# pic32.net
KiCad netlist of a schematic drawn in EAGLE
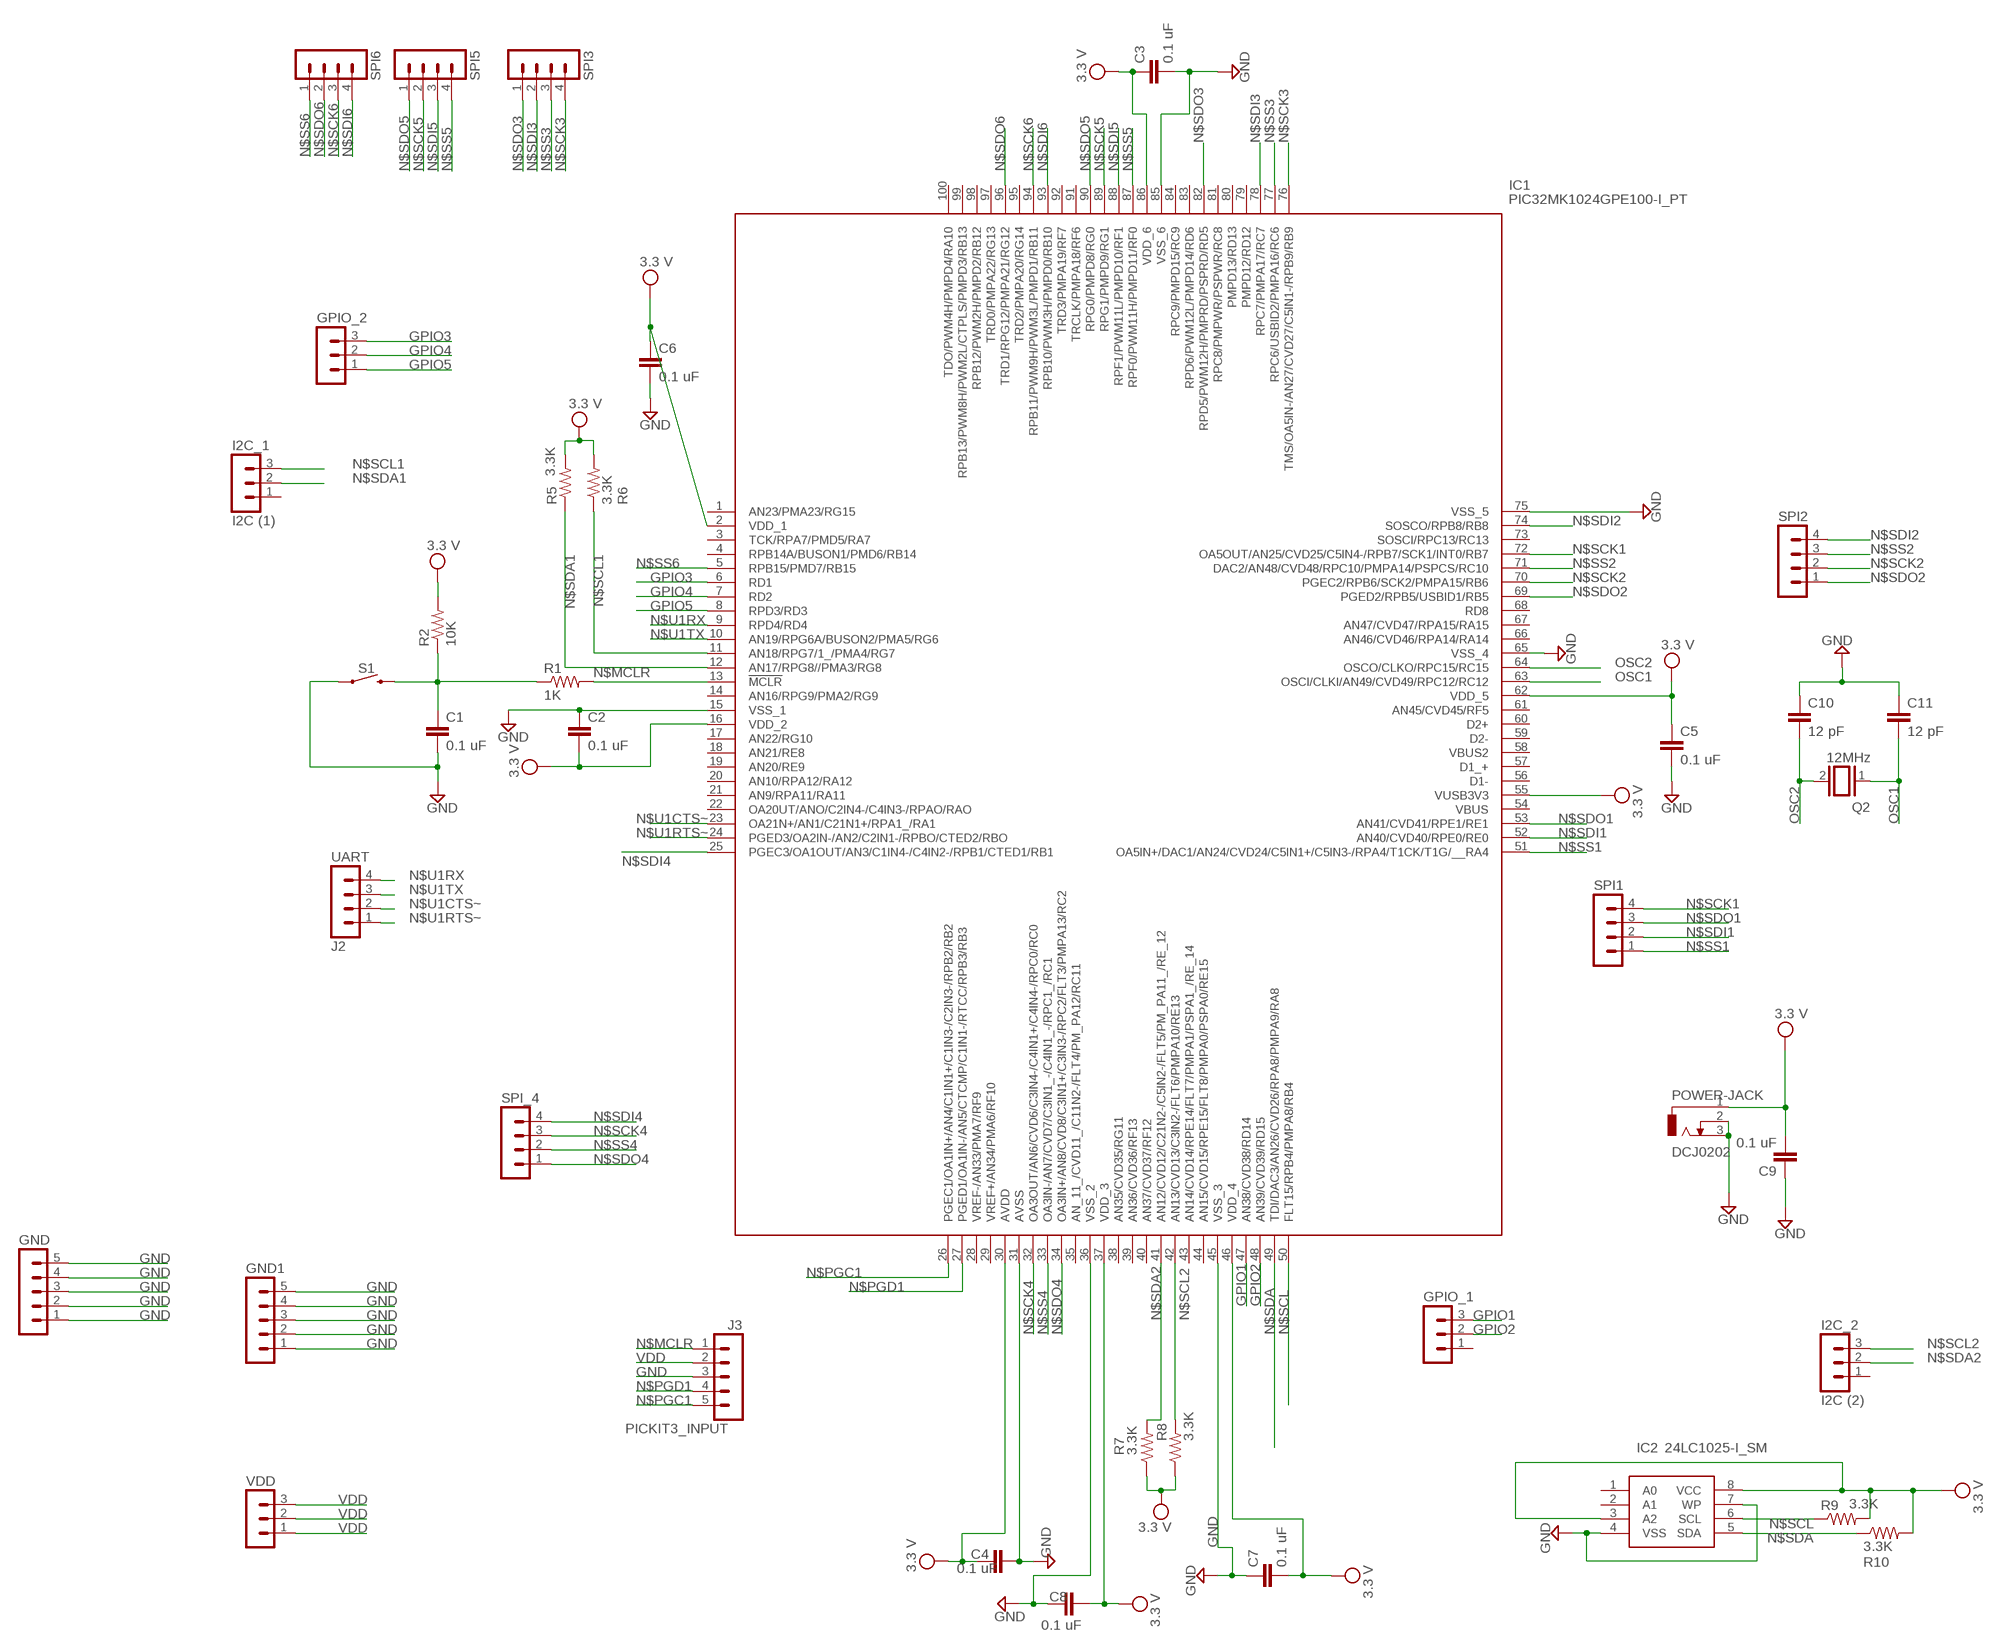
[diagram p0: schematic, sheet 1, part 1 of 2]
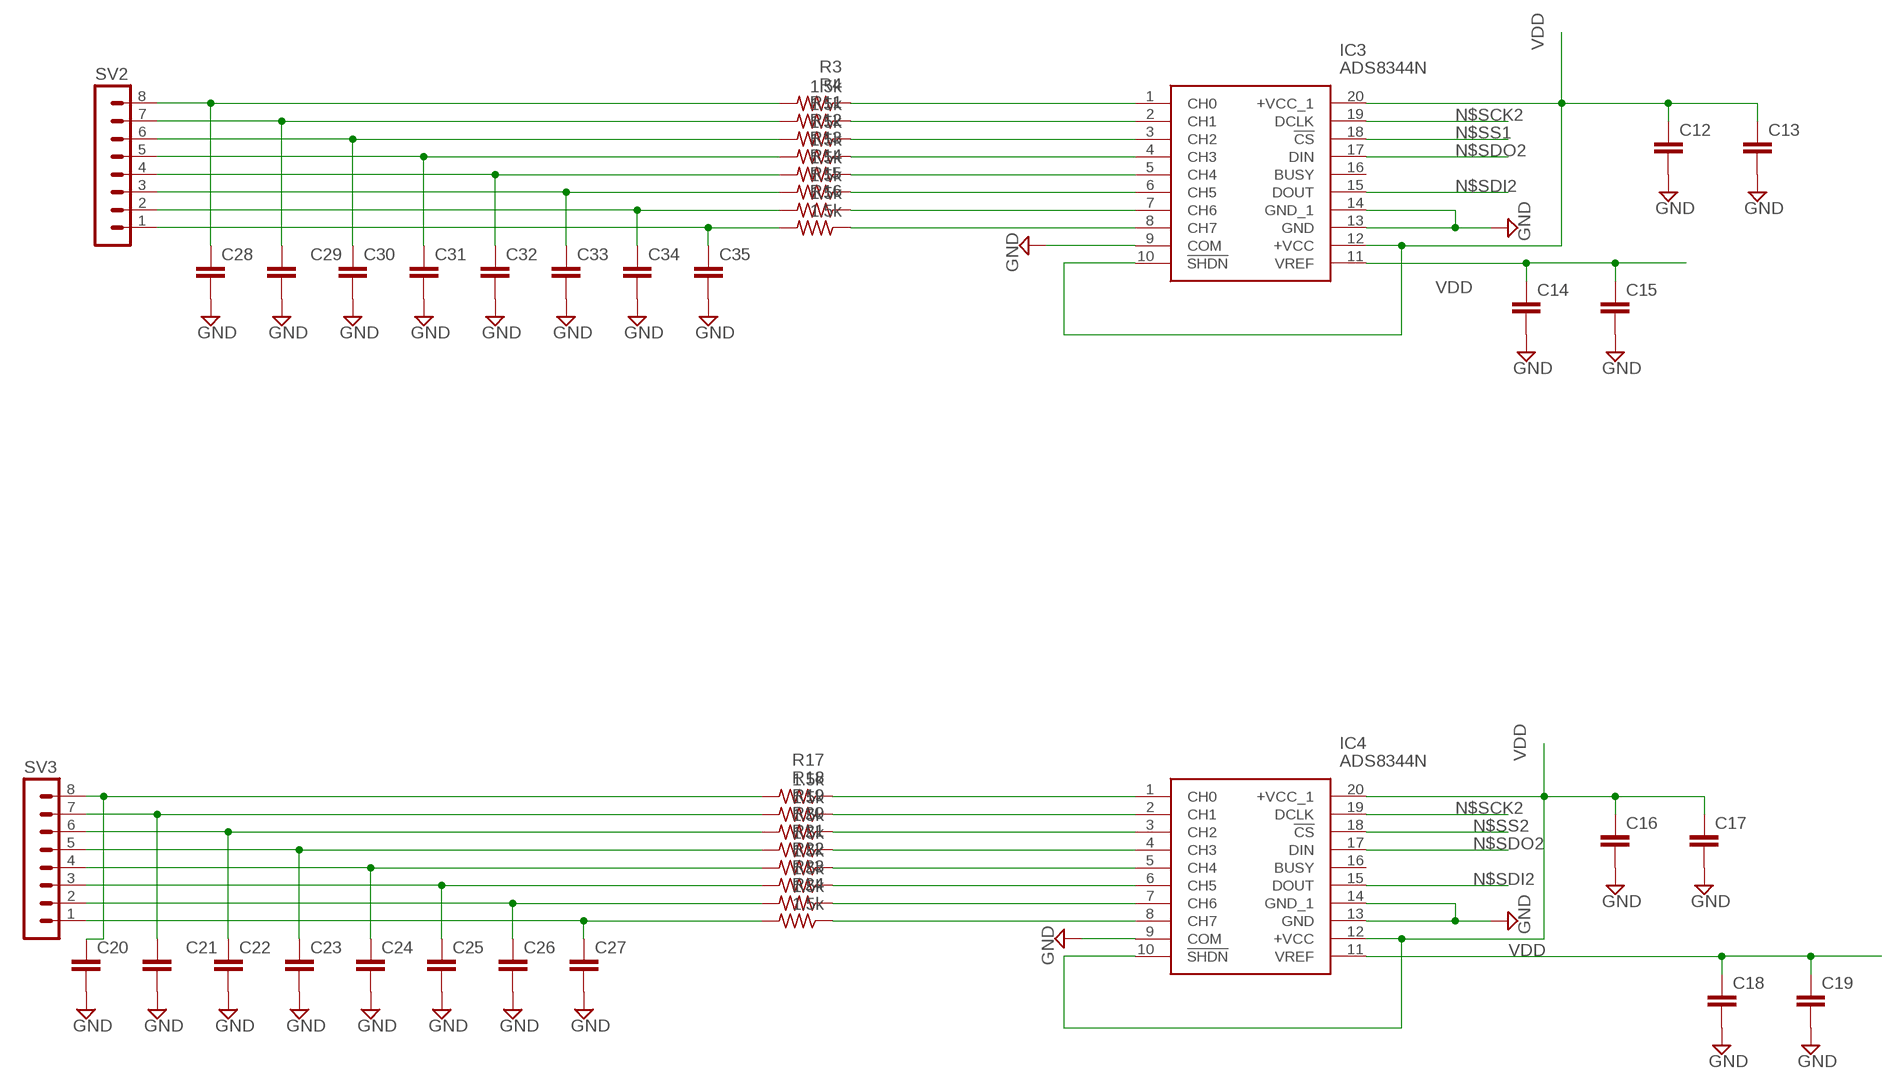
[diagram p1: schematic, sheet 1, part 2 of 2]

(export (version "E")
  (design (tool "Eeschema 10.0.6"))
  (components
    (comp (ref "C1")
      (value "0.1 uF")
      (footprint "eagle-import:C025-025X050")
      (libsource (lib "eagle-import") (part "C-EU025-025X050"))
    )
    (comp (ref "C2")
      (value "0.1 uF")
      (footprint "eagle-import:C025-025X050")
      (libsource (lib "eagle-import") (part "C-EU025-025X050"))
    )
    (comp (ref "C3")
      (value "0.1 uF")
      (footprint "eagle-import:C025-025X050")
      (libsource (lib "eagle-import") (part "C-EU025-025X050"))
    )
    (comp (ref "C4")
      (value "0.1 uF")
      (footprint "eagle-import:C025-025X050")
      (libsource (lib "eagle-import") (part "C-EU025-025X050"))
    )
    (comp (ref "C5")
      (value "0.1 uF")
      (footprint "eagle-import:C025-025X050")
      (libsource (lib "eagle-import") (part "C-EU025-025X050"))
    )
    (comp (ref "C6")
      (value "0.1 uF")
      (footprint "eagle-import:C025-025X050")
      (libsource (lib "eagle-import") (part "C-EU025-025X050"))
    )
    (comp (ref "C7")
      (value "0.1 uF")
      (footprint "eagle-import:C025-025X050")
      (libsource (lib "eagle-import") (part "C-EU025-025X050"))
    )
    (comp (ref "C8")
      (value "0.1 uF")
      (footprint "eagle-import:C025-025X050")
      (libsource (lib "eagle-import") (part "C-EU025-025X050"))
    )
    (comp (ref "C9")
      (value "0.1 uF")
      (footprint "eagle-import:C025-025X050")
      (libsource (lib "eagle-import") (part "C-EU025-025X050"))
    )
    (comp (ref "C10")
      (value "12 pF")
      (footprint "eagle-import:C025-025X050")
      (libsource (lib "eagle-import") (part "C-EU025-025X050"))
    )
    (comp (ref "C11")
      (value "12 pF")
      (footprint "eagle-import:C025-025X050")
      (libsource (lib "eagle-import") (part "C-EU025-025X050"))
    )
    (comp (ref "C12")
      (value "0.1 uF")
      (footprint "eagle-import:C025-025X050")
      (libsource (lib "eagle-import") (part "C-EU025-025X050"))
    )
    (comp (ref "C13")
      (value "0.1 uF")
      (footprint "eagle-import:C025-025X050")
      (libsource (lib "eagle-import") (part "C-EU025-025X050"))
    )
    (comp (ref "C14")
      (value "0.1 uF")
      (footprint "eagle-import:C025-025X050")
      (libsource (lib "eagle-import") (part "C-EU025-025X050"))
    )
    (comp (ref "C15")
      (value "0.1 uF")
      (footprint "eagle-import:C025-025X050")
      (libsource (lib "eagle-import") (part "C-EU025-025X050"))
    )
    (comp (ref "C16")
      (value "0.1 uF")
      (footprint "eagle-import:C025-025X050")
      (libsource (lib "eagle-import") (part "C-EU025-025X050"))
    )
    (comp (ref "C17")
      (value "0.1 uF")
      (footprint "eagle-import:C025-025X050")
      (libsource (lib "eagle-import") (part "C-EU025-025X050"))
    )
    (comp (ref "C18")
      (value "0.1 uF")
      (footprint "eagle-import:C025-025X050")
      (libsource (lib "eagle-import") (part "C-EU025-025X050"))
    )
    (comp (ref "C19")
      (value "0.1 uF")
      (footprint "eagle-import:C025-025X050")
      (libsource (lib "eagle-import") (part "C-EU025-025X050"))
    )
    (comp (ref "C20")
      (value "0.1 uF")
      (footprint "eagle-import:C025-025X050")
      (libsource (lib "eagle-import") (part "C-EU025-025X050"))
    )
    (comp (ref "C21")
      (value "0.1 uF")
      (footprint "eagle-import:C025-025X050")
      (libsource (lib "eagle-import") (part "C-EU025-025X050"))
    )
    (comp (ref "C22")
      (value "0.1 uF")
      (footprint "eagle-import:C025-025X050")
      (libsource (lib "eagle-import") (part "C-EU025-025X050"))
    )
    (comp (ref "C23")
      (value "0.1 uF")
      (footprint "eagle-import:C025-025X050")
      (libsource (lib "eagle-import") (part "C-EU025-025X050"))
    )
    (comp (ref "C24")
      (value "0.1 uF")
      (footprint "eagle-import:C025-025X050")
      (libsource (lib "eagle-import") (part "C-EU025-025X050"))
    )
    (comp (ref "C25")
      (value "0.1 uF")
      (footprint "eagle-import:C025-025X050")
      (libsource (lib "eagle-import") (part "C-EU025-025X050"))
    )
    (comp (ref "C26")
      (value "0.1 uF")
      (footprint "eagle-import:C025-025X050")
      (libsource (lib "eagle-import") (part "C-EU025-025X050"))
    )
    (comp (ref "C27")
      (value "0.1 uF")
      (footprint "eagle-import:C025-025X050")
      (libsource (lib "eagle-import") (part "C-EU025-025X050"))
    )
    (comp (ref "C28")
      (value "0.1 uF")
      (footprint "eagle-import:C025-025X050")
      (libsource (lib "eagle-import") (part "C-EU025-025X050"))
    )
    (comp (ref "C29")
      (value "0.1 uF")
      (footprint "eagle-import:C025-025X050")
      (libsource (lib "eagle-import") (part "C-EU025-025X050"))
    )
    (comp (ref "C30")
      (value "0.1 uF")
      (footprint "eagle-import:C025-025X050")
      (libsource (lib "eagle-import") (part "C-EU025-025X050"))
    )
    (comp (ref "C31")
      (value "0.1 uF")
      (footprint "eagle-import:C025-025X050")
      (libsource (lib "eagle-import") (part "C-EU025-025X050"))
    )
    (comp (ref "C32")
      (value "0.1 uF")
      (footprint "eagle-import:C025-025X050")
      (libsource (lib "eagle-import") (part "C-EU025-025X050"))
    )
    (comp (ref "C33")
      (value "0.1 uF")
      (footprint "eagle-import:C025-025X050")
      (libsource (lib "eagle-import") (part "C-EU025-025X050"))
    )
    (comp (ref "C34")
      (value "0.1 uF")
      (footprint "eagle-import:C025-025X050")
      (libsource (lib "eagle-import") (part "C-EU025-025X050"))
    )
    (comp (ref "C35")
      (value "0.1 uF")
      (footprint "eagle-import:C025-025X050")
      (libsource (lib "eagle-import") (part "C-EU025-025X050"))
    )
    (comp (ref "GND")
      (value "MA05-1")
      (footprint "eagle-import:MA05-1")
      (libsource (lib "eagle-import") (part "MA05-1"))
    )
    (comp (ref "GND1")
      (value "MA05-1")
      (footprint "eagle-import:MA05-1")
      (libsource (lib "eagle-import") (part "MA05-1"))
    )
    (comp (ref "GPIO_1")
      (value "MA03-1")
      (footprint "eagle-import:MA03-1")
      (libsource (lib "eagle-import") (part "MA03-1"))
    )
    (comp (ref "GPIO_2")
      (value "MA03-1")
      (footprint "eagle-import:MA03-1")
      (libsource (lib "eagle-import") (part "MA03-1"))
    )
    (comp (ref "I2C_1")
      (value "I2C (1)")
      (footprint "eagle-import:MA03-1")
      (libsource (lib "eagle-import") (part "MA03-1"))
    )
    (comp (ref "I2C_2")
      (value "I2C (2)")
      (footprint "eagle-import:MA03-1")
      (libsource (lib "eagle-import") (part "MA03-1"))
    )
    (comp (ref "IC1")
      (value "PIC32MK1024GPE100-I_PT")
      (footprint "eagle-import:QFP40P1400X1400X120-100N")
      (fields
        (field (name "MANUFACTURER_PART_NUMBER") "PIC32MK1024GPE100-I/PT")
        (field (name "MOUSER_PART_NUMBER") "579-2MK1024GPE100IPT")
      )
      (libsource (lib "eagle-import") (part "PIC32MK1024GPE100-I_PT"))
    )
    (comp (ref "IC2")
      (value "24LC1025-I_SM")
      (footprint "eagle-import:SOIC127P794X203-8N")
      (fields
        (field (name "MANUFACTURER_PART_NUMBER") "24LC1025-I/SM")
        (field (name "MOUSER_PART_NUMBER") "579-24LC1025-I/SM")
      )
      (libsource (lib "eagle-import") (part "24LC1025-I_SM"))
    )
    (comp (ref "IC3")
      (value "ADS8344N")
      (footprint "eagle-import:SOP65P780X200-20N")
      (fields (field (name "MOUSER_PART_NUMBER") "595-ADS8344N"))
      (libsource (lib "eagle-import") (part "ADS8344N"))
    )
    (comp (ref "IC4")
      (value "ADS8344N")
      (footprint "eagle-import:SOP65P780X200-20N")
      (fields (field (name "MOUSER_PART_NUMBER") "595-ADS8344N"))
      (libsource (lib "eagle-import") (part "ADS8344N"))
    )
    (comp (ref "PICKIT3_INPUT")
      (value "J3")
      (footprint "eagle-import:MA05-1")
      (libsource (lib "eagle-import") (part "MA05-1"))
    )
    (comp (ref "POWER-JACK")
      (value "DCJ0202")
      (footprint "eagle-import:DCJ0202")
      (libsource (lib "eagle-import") (part "DCJ0202"))
    )
    (comp (ref "Q2")
      (value "12MHz")
      (footprint "eagle-import:QS")
      (libsource (lib "eagle-import") (part "XTAL/S"))
    )
    (comp (ref "R1")
      (value "1K")
      (footprint "eagle-import:0207_7")
      (libsource (lib "eagle-import") (part "R-US_0207/7"))
    )
    (comp (ref "R2")
      (value "10K")
      (footprint "eagle-import:0207_7")
      (libsource (lib "eagle-import") (part "R-US_0207/7"))
    )
    (comp (ref "R3")
      (value "1.5k")
      (footprint "eagle-import:0207_7")
      (libsource (lib "eagle-import") (part "R-US_0207/7"))
    )
    (comp (ref "R4")
      (value "1.5k")
      (footprint "eagle-import:0207_7")
      (libsource (lib "eagle-import") (part "R-US_0207/7"))
    )
    (comp (ref "R5")
      (value "3.3K")
      (footprint "eagle-import:0207_7")
      (libsource (lib "eagle-import") (part "R-US_0207/7"))
    )
    (comp (ref "R6")
      (value "3.3K")
      (footprint "eagle-import:0207_7")
      (libsource (lib "eagle-import") (part "R-US_0207/7"))
    )
    (comp (ref "R7")
      (value "3.3K")
      (footprint "eagle-import:0207_7")
      (libsource (lib "eagle-import") (part "R-US_0207/7"))
    )
    (comp (ref "R8")
      (value "3.3K")
      (footprint "eagle-import:0207_7")
      (libsource (lib "eagle-import") (part "R-US_0207/7"))
    )
    (comp (ref "R9")
      (value "3.3K")
      (footprint "eagle-import:0207_7")
      (libsource (lib "eagle-import") (part "R-US_0207/7"))
    )
    (comp (ref "R10")
      (value "3.3K")
      (footprint "eagle-import:0207_7")
      (libsource (lib "eagle-import") (part "R-US_0207/7"))
    )
    (comp (ref "R11")
      (value "1.5k")
      (footprint "eagle-import:0207_7")
      (libsource (lib "eagle-import") (part "R-US_0207/7"))
    )
    (comp (ref "R12")
      (value "1.5k")
      (footprint "eagle-import:0207_7")
      (libsource (lib "eagle-import") (part "R-US_0207/7"))
    )
    (comp (ref "R13")
      (value "1.5k")
      (footprint "eagle-import:0207_7")
      (libsource (lib "eagle-import") (part "R-US_0207/7"))
    )
    (comp (ref "R14")
      (value "1.5k")
      (footprint "eagle-import:0207_7")
      (libsource (lib "eagle-import") (part "R-US_0207/7"))
    )
    (comp (ref "R15")
      (value "1.5k")
      (footprint "eagle-import:0207_7")
      (libsource (lib "eagle-import") (part "R-US_0207/7"))
    )
    (comp (ref "R16")
      (value "1.5k")
      (footprint "eagle-import:0207_7")
      (libsource (lib "eagle-import") (part "R-US_0207/7"))
    )
    (comp (ref "R17")
      (value "1.5k")
      (footprint "eagle-import:0207_7")
      (libsource (lib "eagle-import") (part "R-US_0207/7"))
    )
    (comp (ref "R18")
      (value "1.5k")
      (footprint "eagle-import:0207_7")
      (libsource (lib "eagle-import") (part "R-US_0207/7"))
    )
    (comp (ref "R19")
      (value "1.5k")
      (footprint "eagle-import:0207_7")
      (libsource (lib "eagle-import") (part "R-US_0207/7"))
    )
    (comp (ref "R20")
      (value "1.5k")
      (footprint "eagle-import:0207_7")
      (libsource (lib "eagle-import") (part "R-US_0207/7"))
    )
    (comp (ref "R21")
      (value "1.5k")
      (footprint "eagle-import:0207_7")
      (libsource (lib "eagle-import") (part "R-US_0207/7"))
    )
    (comp (ref "R22")
      (value "1.5k")
      (footprint "eagle-import:0207_7")
      (libsource (lib "eagle-import") (part "R-US_0207/7"))
    )
    (comp (ref "R23")
      (value "1.5k")
      (footprint "eagle-import:0207_7")
      (libsource (lib "eagle-import") (part "R-US_0207/7"))
    )
    (comp (ref "R24")
      (value "1.5k")
      (footprint "eagle-import:0207_7")
      (libsource (lib "eagle-import") (part "R-US_0207/7"))
    )
    (comp (ref "S1")
      (value "MOMENTARY-SWITCH-SPST-SMD-6.2MM-TALL")
      (footprint "eagle-import:TACTILE_SWITCH_SMD_6.2MM_TALL")
      (libsource (lib "eagle-import") (part "MOMENTARY-SWITCH-SPST-SMD-6.2MM-TALL"))
    )
    (comp (ref "SPI1")
      (value "MA04-1")
      (footprint "eagle-import:MA04-1")
      (libsource (lib "eagle-import") (part "MA04-1"))
    )
    (comp (ref "SPI2")
      (value "MA04-1")
      (footprint "eagle-import:MA04-1")
      (libsource (lib "eagle-import") (part "MA04-1"))
    )
    (comp (ref "SPI3")
      (value "MA04-1")
      (footprint "eagle-import:MA04-1")
      (libsource (lib "eagle-import") (part "MA04-1"))
    )
    (comp (ref "SPI5")
      (value "MA04-1")
      (footprint "eagle-import:MA04-1")
      (libsource (lib "eagle-import") (part "MA04-1"))
    )
    (comp (ref "SPI6")
      (value "MA04-1")
      (footprint "eagle-import:MA04-1")
      (libsource (lib "eagle-import") (part "MA04-1"))
    )
    (comp (ref "SPI_4")
      (value "MA04-1")
      (footprint "eagle-import:MA04-1")
      (libsource (lib "eagle-import") (part "MA04-1"))
    )
    (comp (ref "SV2")
      (value "MA08-1")
      (footprint "eagle-import:MA08-1")
      (libsource (lib "eagle-import") (part "MA08-1"))
    )
    (comp (ref "SV3")
      (value "MA08-1")
      (footprint "eagle-import:MA08-1")
      (libsource (lib "eagle-import") (part "MA08-1"))
    )
    (comp (ref "UART")
      (value "J2")
      (footprint "eagle-import:MA04-1")
      (libsource (lib "eagle-import") (part "MA04-1"))
    )
    (comp (ref "VDD")
      (value "MA03-1")
      (footprint "eagle-import:MA03-1")
      (libsource (lib "eagle-import") (part "MA03-1"))
    )
  )
  (nets
    (net (code "1") (name "/GPIO1") (class "Default")
      (node (ref "GPIO_1") (pin "3") (pinfunction "3_3") (pintype "passive"))
      (node (ref "IC1") (pin "47") (pinfunction "AN38/CVD38/RD14_47") (pintype "bidirectional"))
    )
    (net (code "2") (name "/GPIO2") (class "Default")
      (node (ref "GPIO_1") (pin "2") (pinfunction "2_2") (pintype "passive"))
      (node (ref "IC1") (pin "48") (pinfunction "AN39/CVD39/RD15_48") (pintype "bidirectional"))
    )
    (net (code "3") (name "/GPIO3") (class "Default")
      (node (ref "GPIO_2") (pin "3") (pinfunction "3_3") (pintype "passive"))
      (node (ref "IC1") (pin "6") (pinfunction "RD1_6") (pintype "bidirectional"))
    )
    (net (code "4") (name "/GPIO4") (class "Default")
      (node (ref "GPIO_2") (pin "2") (pinfunction "2_2") (pintype "passive"))
      (node (ref "IC1") (pin "7") (pinfunction "RD2_7") (pintype "bidirectional"))
    )
    (net (code "5") (name "/GPIO5") (class "Default")
      (node (ref "GPIO_2") (pin "1") (pinfunction "1_1") (pintype "passive"))
      (node (ref "IC1") (pin "8") (pinfunction "RPD3/RD3_8") (pintype "bidirectional"))
    )
    (net (code "6") (name "/N$MCLR") (class "Default")
      (node (ref "IC1") (pin "13") (pinfunction "~{MCLR}_13") (pintype "bidirectional"))
      (node (ref "PICKIT3_INPUT") (pin "1") (pinfunction "1_1") (pintype "passive"))
      (node (ref "R1") (pin "2") (pinfunction "2_2") (pintype "passive"))
    )
    (net (code "7") (name "/N$PGC1") (class "Default")
      (node (ref "IC1") (pin "26") (pinfunction "PGEC1/OA1IN+/AN4/C1IN1+/C1IN3-/C2IN3-/RPB2/RB2_26") (pintype "bidirectional"))
      (node (ref "PICKIT3_INPUT") (pin "5") (pinfunction "5_5") (pintype "passive"))
    )
    (net (code "8") (name "/N$PGD1") (class "Default")
      (node (ref "IC1") (pin "27") (pinfunction "PGED1/OA1IN-/AN5/CTCMP/C1IN1-/RTCC/RPB3/RB3_27") (pintype "bidirectional"))
      (node (ref "PICKIT3_INPUT") (pin "4") (pinfunction "4_4") (pintype "passive"))
    )
    (net (code "9") (name "/N$SCK1") (class "Default")
      (node (ref "IC1") (pin "72") (pinfunction "OA5OUT/AN25/CVD25/C5IN4-/RPB7/SCK1/INT0/RB7_72") (pintype "bidirectional"))
      (node (ref "SPI1") (pin "4") (pinfunction "4_4") (pintype "passive"))
    )
    (net (code "10") (name "/N$SCK2") (class "Default")
      (node (ref "IC1") (pin "70") (pinfunction "PGEC2/RPB6/SCK2/PMPA15/RB6_70") (pintype "bidirectional"))
      (node (ref "IC3") (pin "19") (pinfunction "DCLK_19") (pintype "input"))
      (node (ref "IC4") (pin "19") (pinfunction "DCLK_19") (pintype "input"))
      (node (ref "SPI2") (pin "2") (pinfunction "2_2") (pintype "passive"))
    )
    (net (code "11") (name "/N$SCK3") (class "Default")
      (node (ref "IC1") (pin "76") (pinfunction "TMS/OA5IN-/AN27/CVD27/C5IN1-/RPB9/RB9_76") (pintype "bidirectional"))
      (node (ref "SPI3") (pin "4") (pinfunction "4_4") (pintype "passive"))
    )
    (net (code "12") (name "/N$SCK4") (class "Default")
      (node (ref "IC1") (pin "32") (pinfunction "OA3OUT/AN6/CVD6/C3IN4-/C4IN1+/C4IN4-/RPC0/RC0_32") (pintype "bidirectional"))
      (node (ref "SPI_4") (pin "3") (pinfunction "3_3") (pintype "passive"))
    )
    (net (code "13") (name "/N$SCK5") (class "Default")
      (node (ref "IC1") (pin "89") (pinfunction "RPG1/PMPD9/RG1_89") (pintype "bidirectional"))
      (node (ref "SPI5") (pin "2") (pinfunction "2_2") (pintype "passive"))
    )
    (net (code "14") (name "/N$SCK6") (class "Default")
      (node (ref "IC1") (pin "94") (pinfunction "RPB11/PWM9H/PWM3L/PMPD1/RB11_94") (pintype "bidirectional"))
      (node (ref "SPI6") (pin "3") (pinfunction "3_3") (pintype "passive"))
    )
    (net (code "15") (name "/N$SCL") (class "Default")
      (node (ref "IC1") (pin "50") (pinfunction "FLT15/RPB4/PMPA8/RB4_50") (pintype "bidirectional"))
      (node (ref "IC2") (pin "6") (pinfunction "SCL_6") (pintype "bidirectional"))
      (node (ref "R9") (pin "1") (pinfunction "1_1") (pintype "passive"))
    )
    (net (code "16") (name "/N$SCL1") (class "Default")
      (node (ref "I2C_1") (pin "3") (pinfunction "3_3") (pintype "passive"))
      (node (ref "IC1") (pin "11") (pinfunction "AN18/RPG7/1_/PMA4/RG7_11") (pintype "bidirectional"))
      (node (ref "R6") (pin "1") (pinfunction "1_1") (pintype "passive"))
    )
    (net (code "17") (name "/N$SCL2") (class "Default")
      (node (ref "I2C_2") (pin "3") (pinfunction "3_3") (pintype "passive"))
      (node (ref "IC1") (pin "42") (pinfunction "AN13/CVD13/C3IN2-/FLT6/PMPA10/RE13_42") (pintype "bidirectional"))
      (node (ref "R8") (pin "2") (pinfunction "2_2") (pintype "passive"))
    )
    (net (code "18") (name "/N$SDA") (class "Default")
      (node (ref "IC1") (pin "49") (pinfunction "TDI/DAC3/AN26/CVD26/RPA8/PMPA9/RA8_49") (pintype "bidirectional"))
      (node (ref "IC2") (pin "5") (pinfunction "SDA_5") (pintype "bidirectional"))
      (node (ref "R10") (pin "1") (pinfunction "1_1") (pintype "passive"))
    )
    (net (code "19") (name "/N$SDA1") (class "Default")
      (node (ref "I2C_1") (pin "2") (pinfunction "2_2") (pintype "passive"))
      (node (ref "IC1") (pin "12") (pinfunction "AN17/RPG8//PMA3/RG8_12") (pintype "bidirectional"))
      (node (ref "R5") (pin "1") (pinfunction "1_1") (pintype "passive"))
    )
    (net (code "20") (name "/N$SDA2") (class "Default")
      (node (ref "I2C_2") (pin "2") (pinfunction "2_2") (pintype "passive"))
      (node (ref "IC1") (pin "41") (pinfunction "AN12/CVD12/C21N2-/C5IN2-/FLT5/PM_PA11_/RE_12_41") (pintype "bidirectional"))
      (node (ref "R7") (pin "2") (pinfunction "2_2") (pintype "passive"))
    )
    (net (code "21") (name "/N$SDI1") (class "Default")
      (node (ref "IC1") (pin "52") (pinfunction "AN40/CVD40/RPE0/RE0_52") (pintype "bidirectional"))
      (node (ref "SPI1") (pin "2") (pinfunction "2_2") (pintype "passive"))
    )
    (net (code "22") (name "/N$SDI2") (class "Default")
      (node (ref "IC1") (pin "74") (pinfunction "SOSCO/RPB8/RB8_74") (pintype "bidirectional"))
      (node (ref "IC3") (pin "15") (pinfunction "DOUT_15") (pintype "output"))
      (node (ref "IC4") (pin "15") (pinfunction "DOUT_15") (pintype "output"))
      (node (ref "SPI2") (pin "4") (pinfunction "4_4") (pintype "passive"))
    )
    (net (code "23") (name "/N$SDI3") (class "Default")
      (node (ref "IC1") (pin "78") (pinfunction "RPC7/PMPA17/RC7_78") (pintype "bidirectional"))
      (node (ref "SPI3") (pin "2") (pinfunction "2_2") (pintype "passive"))
    )
    (net (code "24") (name "/N$SDI4") (class "Default")
      (node (ref "IC1") (pin "25") (pinfunction "PGEC3/OA1OUT/AN3/C1IN4-/C4IN2-/RPB1/CTED1/RB1_25") (pintype "bidirectional"))
      (node (ref "SPI_4") (pin "4") (pinfunction "4_4") (pintype "passive"))
    )
    (net (code "25") (name "/N$SDI5") (class "Default")
      (node (ref "IC1") (pin "88") (pinfunction "RPF1/PWM11L/PMPD10/RF1_88") (pintype "bidirectional"))
      (node (ref "SPI5") (pin "3") (pinfunction "3_3") (pintype "passive"))
    )
    (net (code "26") (name "/N$SDI6") (class "Default")
      (node (ref "IC1") (pin "93") (pinfunction "RPB10/PWM3H/PMPD0/RB10_93") (pintype "bidirectional"))
      (node (ref "SPI6") (pin "4") (pinfunction "4_4") (pintype "passive"))
    )
    (net (code "27") (name "/N$SDO1") (class "Default")
      (node (ref "IC1") (pin "53") (pinfunction "AN41/CVD41/RPE1/RE1_53") (pintype "bidirectional"))
      (node (ref "SPI1") (pin "3") (pinfunction "3_3") (pintype "passive"))
    )
    (net (code "28") (name "/N$SDO2") (class "Default")
      (node (ref "IC1") (pin "69") (pinfunction "PGED2/RPB5/USBID1/RB5_69") (pintype "bidirectional"))
      (node (ref "IC3") (pin "17") (pinfunction "DIN_17") (pintype "input"))
      (node (ref "IC4") (pin "17") (pinfunction "DIN_17") (pintype "input"))
      (node (ref "SPI2") (pin "1") (pinfunction "1_1") (pintype "passive"))
    )
    (net (code "29") (name "/N$SDO3") (class "Default")
      (node (ref "IC1") (pin "82") (pinfunction "RPD5/PWM12H/PMPRD/PSPRD/RD5_82") (pintype "bidirectional"))
      (node (ref "SPI3") (pin "1") (pinfunction "1_1") (pintype "passive"))
    )
    (net (code "30") (name "/N$SDO4") (class "Default")
      (node (ref "IC1") (pin "34") (pinfunction "OA3IN+/AN8/CVD8/C3IN1+/C3IN3-/RPC2/FLT3/PMPA13/RC2_34") (pintype "bidirectional"))
      (node (ref "SPI_4") (pin "1") (pinfunction "1_1") (pintype "passive"))
    )
    (net (code "31") (name "/N$SDO5") (class "Default")
      (node (ref "IC1") (pin "90") (pinfunction "RPG0/PMPD8/RG0_90") (pintype "bidirectional"))
      (node (ref "SPI5") (pin "1") (pinfunction "1_1") (pintype "passive"))
    )
    (net (code "32") (name "/N$SDO6") (class "Default")
      (node (ref "IC1") (pin "96") (pinfunction "TRD1/RPG12/PMPA21/RG12_96") (pintype "bidirectional"))
      (node (ref "SPI6") (pin "2") (pinfunction "2_2") (pintype "passive"))
    )
    (net (code "33") (name "/N$SS1") (class "Default")
      (node (ref "IC1") (pin "51") (pinfunction "OA5IN+/DAC1/AN24/CVD24/C5IN1+/C5IN3-/RPA4/T1CK/T1G/__RA4_51") (pintype "bidirectional"))
      (node (ref "IC3") (pin "18") (pinfunction "~{CS}_18") (pintype "input"))
      (node (ref "SPI1") (pin "1") (pinfunction "1_1") (pintype "passive"))
    )
    (net (code "34") (name "/N$SS2") (class "Default")
      (node (ref "IC1") (pin "71") (pinfunction "DAC2/AN48/CVD48/RPC10/PMPA14/PSPCS/RC10_71") (pintype "bidirectional"))
      (node (ref "IC4") (pin "18") (pinfunction "~{CS}_18") (pintype "input"))
      (node (ref "SPI2") (pin "3") (pinfunction "3_3") (pintype "passive"))
    )
    (net (code "35") (name "/N$SS3") (class "Default")
      (node (ref "IC1") (pin "77") (pinfunction "RPC6/USBID2/PMPA16/RC6_77") (pintype "bidirectional"))
      (node (ref "SPI3") (pin "3") (pinfunction "3_3") (pintype "passive"))
    )
    (net (code "36") (name "/N$SS4") (class "Default")
      (node (ref "IC1") (pin "33") (pinfunction "OA3IN-/AN7/CVD7/C3IN1_-/C4IN1_-/RPC1_/RC1_33") (pintype "bidirectional"))
      (node (ref "SPI_4") (pin "2") (pinfunction "2_2") (pintype "passive"))
    )
    (net (code "37") (name "/N$SS5") (class "Default")
      (node (ref "IC1") (pin "87") (pinfunction "RPF0/PWM11H/PMPD11/RF0_87") (pintype "bidirectional"))
      (node (ref "SPI5") (pin "4") (pinfunction "4_4") (pintype "passive"))
    )
    (net (code "38") (name "/N$SS6") (class "Default")
      (node (ref "IC1") (pin "5") (pinfunction "RPB15/PMD7/RB15_5") (pintype "bidirectional"))
      (node (ref "SPI6") (pin "1") (pinfunction "1_1") (pintype "passive"))
    )
    (net (code "39") (name "/N$U1CTS~{}") (class "Default")
      (node (ref "IC1") (pin "23") (pinfunction "OA21N+/AN1/C21N1+/RPA1_/RA1_23") (pintype "bidirectional"))
      (node (ref "UART") (pin "2") (pinfunction "2_2") (pintype "passive"))
    )
    (net (code "40") (name "/N$U1RTS~{}") (class "Default")
      (node (ref "IC1") (pin "24") (pinfunction "PGED3/OA2IN-/AN2/C2IN1-/RPBO/CTED2/RBO_24") (pintype "bidirectional"))
      (node (ref "UART") (pin "1") (pinfunction "1_1") (pintype "passive"))
    )
    (net (code "41") (name "/N$U1RX") (class "Default")
      (node (ref "IC1") (pin "9") (pinfunction "RPD4/RD4_9") (pintype "bidirectional"))
      (node (ref "UART") (pin "4") (pinfunction "4_4") (pintype "passive"))
    )
    (net (code "42") (name "/N$U1TX") (class "Default")
      (node (ref "IC1") (pin "10") (pinfunction "AN19/RPG6A/BUSON2/PMA5/RG6_10") (pintype "bidirectional"))
      (node (ref "UART") (pin "3") (pinfunction "3_3") (pintype "passive"))
    )
    (net (code "43") (name "/OSC1") (class "Default")
      (node (ref "C11") (pin "2") (pinfunction "2_2") (pintype "passive"))
      (node (ref "IC1") (pin "63") (pinfunction "OSCI/CLKI/AN49/CVD49/RPC12/RC12_63") (pintype "bidirectional"))
      (node (ref "Q2") (pin "1") (pinfunction "1_1") (pintype "passive"))
    )
    (net (code "44") (name "/OSC2") (class "Default")
      (node (ref "C10") (pin "2") (pinfunction "2_2") (pintype "passive"))
      (node (ref "IC1") (pin "64") (pinfunction "OSCO/CLKO/RPC15/RC15_64") (pintype "bidirectional"))
      (node (ref "Q2") (pin "2") (pinfunction "2_2") (pintype "passive"))
    )
    (net (code "45") (name "3.3 V") (class "Default")
      (node (ref "C12") (pin "1") (pinfunction "1_1") (pintype "passive"))
      (node (ref "C13") (pin "1") (pinfunction "1_1") (pintype "passive"))
      (node (ref "C14") (pin "1") (pinfunction "1_1") (pintype "passive"))
      (node (ref "C15") (pin "1") (pinfunction "1_1") (pintype "passive"))
      (node (ref "C16") (pin "1") (pinfunction "1_1") (pintype "passive"))
      (node (ref "C17") (pin "1") (pinfunction "1_1") (pintype "passive"))
      (node (ref "C18") (pin "1") (pinfunction "1_1") (pintype "passive"))
      (node (ref "C19") (pin "1") (pinfunction "1_1") (pintype "passive"))
      (node (ref "C2") (pin "2") (pinfunction "2_2") (pintype "passive"))
      (node (ref "C3") (pin "1") (pinfunction "1_1") (pintype "passive"))
      (node (ref "C4") (pin "2") (pinfunction "2_2") (pintype "passive"))
      (node (ref "C5") (pin "1") (pinfunction "1_1") (pintype "passive"))
      (node (ref "C6") (pin "1") (pinfunction "1_1") (pintype "passive"))
      (node (ref "C7") (pin "2") (pinfunction "2_2") (pintype "passive"))
      (node (ref "C8") (pin "2") (pinfunction "2_2") (pintype "passive"))
      (node (ref "C9") (pin "2") (pinfunction "2_2") (pintype "passive"))
      (node (ref "IC1") (pin "16") (pinfunction "VDD_2_16") (pintype "bidirectional"))
      (node (ref "IC1") (pin "2") (pinfunction "VDD_1_2") (pintype "bidirectional"))
      (node (ref "IC1") (pin "30") (pinfunction "AVDD_30") (pintype "bidirectional"))
      (node (ref "IC1") (pin "37") (pinfunction "VDD_3_37") (pintype "bidirectional"))
      (node (ref "IC1") (pin "46") (pinfunction "VDD_4_46") (pintype "bidirectional"))
      (node (ref "IC1") (pin "55") (pinfunction "VUSB3V3_55") (pintype "bidirectional"))
      (node (ref "IC1") (pin "62") (pinfunction "VDD_5_62") (pintype "bidirectional"))
      (node (ref "IC1") (pin "86") (pinfunction "VDD_6_86") (pintype "bidirectional"))
      (node (ref "IC2") (pin "3") (pinfunction "A2_3") (pintype "bidirectional"))
      (node (ref "IC2") (pin "8") (pinfunction "VCC_8") (pintype "power_in"))
      (node (ref "IC3") (pin "10") (pinfunction "~{SHDN}_10") (pintype "bidirectional"))
      (node (ref "IC3") (pin "11") (pinfunction "VREF_11") (pintype "input"))
      (node (ref "IC3") (pin "12") (pinfunction "+VCC_12") (pintype "power_in"))
      (node (ref "IC3") (pin "20") (pinfunction "+VCC_1_20") (pintype "power_in"))
      (node (ref "IC4") (pin "10") (pinfunction "~{SHDN}_10") (pintype "bidirectional"))
      (node (ref "IC4") (pin "11") (pinfunction "VREF_11") (pintype "input"))
      (node (ref "IC4") (pin "12") (pinfunction "+VCC_12") (pintype "power_in"))
      (node (ref "IC4") (pin "20") (pinfunction "+VCC_1_20") (pintype "power_in"))
      (node (ref "PICKIT3_INPUT") (pin "2") (pinfunction "2_2") (pintype "passive"))
      (node (ref "POWER-JACK") (pin "1") (pinfunction "1_1") (pintype "passive"))
      (node (ref "R10") (pin "2") (pinfunction "2_2") (pintype "passive"))
      (node (ref "R2") (pin "2") (pinfunction "2_2") (pintype "passive"))
      (node (ref "R5") (pin "2") (pinfunction "2_2") (pintype "passive"))
      (node (ref "R6") (pin "2") (pinfunction "2_2") (pintype "passive"))
      (node (ref "R7") (pin "1") (pinfunction "1_1") (pintype "passive"))
      (node (ref "R8") (pin "1") (pinfunction "1_1") (pintype "passive"))
      (node (ref "R9") (pin "2") (pinfunction "2_2") (pintype "passive"))
      (node (ref "VDD") (pin "1") (pinfunction "1_1") (pintype "passive"))
      (node (ref "VDD") (pin "2") (pinfunction "2_2") (pintype "passive"))
      (node (ref "VDD") (pin "3") (pinfunction "3_3") (pintype "passive"))
    )
    (net (code "46") (name "GND") (class "Default")
      (node (ref "C1") (pin "2") (pinfunction "2_2") (pintype "passive"))
      (node (ref "C10") (pin "1") (pinfunction "1_1") (pintype "passive"))
      (node (ref "C11") (pin "1") (pinfunction "1_1") (pintype "passive"))
      (node (ref "C12") (pin "2") (pinfunction "2_2") (pintype "passive"))
      (node (ref "C13") (pin "2") (pinfunction "2_2") (pintype "passive"))
      (node (ref "C14") (pin "2") (pinfunction "2_2") (pintype "passive"))
      (node (ref "C15") (pin "2") (pinfunction "2_2") (pintype "passive"))
      (node (ref "C16") (pin "2") (pinfunction "2_2") (pintype "passive"))
      (node (ref "C17") (pin "2") (pinfunction "2_2") (pintype "passive"))
      (node (ref "C18") (pin "2") (pinfunction "2_2") (pintype "passive"))
      (node (ref "C19") (pin "2") (pinfunction "2_2") (pintype "passive"))
      (node (ref "C2") (pin "1") (pinfunction "1_1") (pintype "passive"))
      (node (ref "C20") (pin "2") (pinfunction "2_2") (pintype "passive"))
      (node (ref "C21") (pin "2") (pinfunction "2_2") (pintype "passive"))
      (node (ref "C22") (pin "2") (pinfunction "2_2") (pintype "passive"))
      (node (ref "C23") (pin "2") (pinfunction "2_2") (pintype "passive"))
      (node (ref "C24") (pin "2") (pinfunction "2_2") (pintype "passive"))
      (node (ref "C25") (pin "2") (pinfunction "2_2") (pintype "passive"))
      (node (ref "C26") (pin "2") (pinfunction "2_2") (pintype "passive"))
      (node (ref "C27") (pin "2") (pinfunction "2_2") (pintype "passive"))
      (node (ref "C28") (pin "2") (pinfunction "2_2") (pintype "passive"))
      (node (ref "C29") (pin "2") (pinfunction "2_2") (pintype "passive"))
      (node (ref "C3") (pin "2") (pinfunction "2_2") (pintype "passive"))
      (node (ref "C30") (pin "2") (pinfunction "2_2") (pintype "passive"))
      (node (ref "C31") (pin "2") (pinfunction "2_2") (pintype "passive"))
      (node (ref "C32") (pin "2") (pinfunction "2_2") (pintype "passive"))
      (node (ref "C33") (pin "2") (pinfunction "2_2") (pintype "passive"))
      (node (ref "C34") (pin "2") (pinfunction "2_2") (pintype "passive"))
      (node (ref "C35") (pin "2") (pinfunction "2_2") (pintype "passive"))
      (node (ref "C4") (pin "1") (pinfunction "1_1") (pintype "passive"))
      (node (ref "C5") (pin "2") (pinfunction "2_2") (pintype "passive"))
      (node (ref "C6") (pin "2") (pinfunction "2_2") (pintype "passive"))
      (node (ref "C7") (pin "1") (pinfunction "1_1") (pintype "passive"))
      (node (ref "C8") (pin "1") (pinfunction "1_1") (pintype "passive"))
      (node (ref "C9") (pin "1") (pinfunction "1_1") (pintype "passive"))
      (node (ref "GND") (pin "1") (pinfunction "1_1") (pintype "passive"))
      (node (ref "GND") (pin "2") (pinfunction "2_2") (pintype "passive"))
      (node (ref "GND") (pin "3") (pinfunction "3_3") (pintype "passive"))
      (node (ref "GND") (pin "4") (pinfunction "4_4") (pintype "passive"))
      (node (ref "GND") (pin "5") (pinfunction "5_5") (pintype "passive"))
      (node (ref "GND1") (pin "1") (pinfunction "1_1") (pintype "passive"))
      (node (ref "GND1") (pin "2") (pinfunction "2_2") (pintype "passive"))
      (node (ref "GND1") (pin "3") (pinfunction "3_3") (pintype "passive"))
      (node (ref "GND1") (pin "4") (pinfunction "4_4") (pintype "passive"))
      (node (ref "GND1") (pin "5") (pinfunction "5_5") (pintype "passive"))
      (node (ref "IC1") (pin "15") (pinfunction "VSS_1_15") (pintype "bidirectional"))
      (node (ref "IC1") (pin "31") (pinfunction "AVSS_31") (pintype "bidirectional"))
      (node (ref "IC1") (pin "36") (pinfunction "VSS_2_36") (pintype "bidirectional"))
      (node (ref "IC1") (pin "45") (pinfunction "VSS_3_45") (pintype "bidirectional"))
      (node (ref "IC1") (pin "65") (pinfunction "VSS_4_65") (pintype "bidirectional"))
      (node (ref "IC1") (pin "75") (pinfunction "VSS_5_75") (pintype "bidirectional"))
      (node (ref "IC1") (pin "85") (pinfunction "VSS_6_85") (pintype "bidirectional"))
      (node (ref "IC2") (pin "4") (pinfunction "VSS_4") (pintype "power_in"))
      (node (ref "IC2") (pin "7") (pinfunction "WP_7") (pintype "bidirectional"))
      (node (ref "IC3") (pin "13") (pinfunction "GND_13") (pintype "power_in"))
      (node (ref "IC3") (pin "14") (pinfunction "GND_1_14") (pintype "power_in"))
      (node (ref "IC3") (pin "9") (pinfunction "COM_9") (pintype "bidirectional"))
      (node (ref "IC4") (pin "13") (pinfunction "GND_13") (pintype "power_in"))
      (node (ref "IC4") (pin "14") (pinfunction "GND_1_14") (pintype "power_in"))
      (node (ref "IC4") (pin "9") (pinfunction "COM_9") (pintype "bidirectional"))
      (node (ref "PICKIT3_INPUT") (pin "3") (pinfunction "3_3") (pintype "passive"))
      (node (ref "POWER-JACK") (pin "2") (pinfunction "2_2") (pintype "passive"))
      (node (ref "POWER-JACK") (pin "3") (pinfunction "3_3") (pintype "passive"))
      (node (ref "S1") (pin "A2") (pinfunction "1_A2") (pintype "passive"))
    )
    (net (code "47") (name "Net-(C20-Pad1)") (class "Default")
      (node (ref "C20") (pin "1") (pinfunction "1_1") (pintype "passive"))
      (node (ref "R17") (pin "2") (pinfunction "2_2") (pintype "passive"))
      (node (ref "SV3") (pin "8") (pinfunction "8_8") (pintype "passive"))
    )
    (net (code "48") (name "Net-(C21-Pad1)") (class "Default")
      (node (ref "C21") (pin "1") (pinfunction "1_1") (pintype "passive"))
      (node (ref "R18") (pin "2") (pinfunction "2_2") (pintype "passive"))
      (node (ref "SV3") (pin "7") (pinfunction "7_7") (pintype "passive"))
    )
    (net (code "49") (name "Net-(C22-Pad1)") (class "Default")
      (node (ref "C22") (pin "1") (pinfunction "1_1") (pintype "passive"))
      (node (ref "R19") (pin "2") (pinfunction "2_2") (pintype "passive"))
      (node (ref "SV3") (pin "6") (pinfunction "6_6") (pintype "passive"))
    )
    (net (code "50") (name "Net-(C23-Pad1)") (class "Default")
      (node (ref "C23") (pin "1") (pinfunction "1_1") (pintype "passive"))
      (node (ref "R20") (pin "2") (pinfunction "2_2") (pintype "passive"))
      (node (ref "SV3") (pin "5") (pinfunction "5_5") (pintype "passive"))
    )
    (net (code "51") (name "Net-(C24-Pad1)") (class "Default")
      (node (ref "C24") (pin "1") (pinfunction "1_1") (pintype "passive"))
      (node (ref "R21") (pin "2") (pinfunction "2_2") (pintype "passive"))
      (node (ref "SV3") (pin "4") (pinfunction "4_4") (pintype "passive"))
    )
    (net (code "52") (name "Net-(C25-Pad1)") (class "Default")
      (node (ref "C25") (pin "1") (pinfunction "1_1") (pintype "passive"))
      (node (ref "R22") (pin "2") (pinfunction "2_2") (pintype "passive"))
      (node (ref "SV3") (pin "3") (pinfunction "3_3") (pintype "passive"))
    )
    (net (code "53") (name "Net-(C26-Pad1)") (class "Default")
      (node (ref "C26") (pin "1") (pinfunction "1_1") (pintype "passive"))
      (node (ref "R23") (pin "2") (pinfunction "2_2") (pintype "passive"))
      (node (ref "SV3") (pin "2") (pinfunction "2_2") (pintype "passive"))
    )
    (net (code "54") (name "Net-(C27-Pad1)") (class "Default")
      (node (ref "C27") (pin "1") (pinfunction "1_1") (pintype "passive"))
      (node (ref "R24") (pin "2") (pinfunction "2_2") (pintype "passive"))
      (node (ref "SV3") (pin "1") (pinfunction "1_1") (pintype "passive"))
    )
    (net (code "55") (name "Net-(C28-Pad1)") (class "Default")
      (node (ref "C28") (pin "1") (pinfunction "1_1") (pintype "passive"))
      (node (ref "R3") (pin "2") (pinfunction "2_2") (pintype "passive"))
      (node (ref "SV2") (pin "8") (pinfunction "8_8") (pintype "passive"))
    )
    (net (code "56") (name "Net-(C29-Pad1)") (class "Default")
      (node (ref "C29") (pin "1") (pinfunction "1_1") (pintype "passive"))
      (node (ref "R4") (pin "2") (pinfunction "2_2") (pintype "passive"))
      (node (ref "SV2") (pin "7") (pinfunction "7_7") (pintype "passive"))
    )
    (net (code "57") (name "Net-(C30-Pad1)") (class "Default")
      (node (ref "C30") (pin "1") (pinfunction "1_1") (pintype "passive"))
      (node (ref "R11") (pin "2") (pinfunction "2_2") (pintype "passive"))
      (node (ref "SV2") (pin "6") (pinfunction "6_6") (pintype "passive"))
    )
    (net (code "58") (name "Net-(C31-Pad1)") (class "Default")
      (node (ref "C31") (pin "1") (pinfunction "1_1") (pintype "passive"))
      (node (ref "R12") (pin "2") (pinfunction "2_2") (pintype "passive"))
      (node (ref "SV2") (pin "5") (pinfunction "5_5") (pintype "passive"))
    )
    (net (code "59") (name "Net-(C32-Pad1)") (class "Default")
      (node (ref "C32") (pin "1") (pinfunction "1_1") (pintype "passive"))
      (node (ref "R13") (pin "2") (pinfunction "2_2") (pintype "passive"))
      (node (ref "SV2") (pin "4") (pinfunction "4_4") (pintype "passive"))
    )
    (net (code "60") (name "Net-(C33-Pad1)") (class "Default")
      (node (ref "C33") (pin "1") (pinfunction "1_1") (pintype "passive"))
      (node (ref "R14") (pin "2") (pinfunction "2_2") (pintype "passive"))
      (node (ref "SV2") (pin "3") (pinfunction "3_3") (pintype "passive"))
    )
    (net (code "61") (name "Net-(C34-Pad1)") (class "Default")
      (node (ref "C34") (pin "1") (pinfunction "1_1") (pintype "passive"))
      (node (ref "R15") (pin "2") (pinfunction "2_2") (pintype "passive"))
      (node (ref "SV2") (pin "2") (pinfunction "2_2") (pintype "passive"))
    )
    (net (code "62") (name "Net-(C35-Pad1)") (class "Default")
      (node (ref "C35") (pin "1") (pinfunction "1_1") (pintype "passive"))
      (node (ref "R16") (pin "2") (pinfunction "2_2") (pintype "passive"))
      (node (ref "SV2") (pin "1") (pinfunction "1_1") (pintype "passive"))
    )
    (net (code "63") (name "Net-(IC3-CH0)") (class "Default")
      (node (ref "IC3") (pin "1") (pinfunction "CH0_1") (pintype "bidirectional"))
      (node (ref "R3") (pin "1") (pinfunction "1_1") (pintype "passive"))
    )
    (net (code "64") (name "Net-(IC3-CH1)") (class "Default")
      (node (ref "IC3") (pin "2") (pinfunction "CH1_2") (pintype "bidirectional"))
      (node (ref "R4") (pin "1") (pinfunction "1_1") (pintype "passive"))
    )
    (net (code "65") (name "Net-(IC3-CH2)") (class "Default")
      (node (ref "IC3") (pin "3") (pinfunction "CH2_3") (pintype "bidirectional"))
      (node (ref "R11") (pin "1") (pinfunction "1_1") (pintype "passive"))
    )
    (net (code "66") (name "Net-(IC3-CH3)") (class "Default")
      (node (ref "IC3") (pin "4") (pinfunction "CH3_4") (pintype "bidirectional"))
      (node (ref "R12") (pin "1") (pinfunction "1_1") (pintype "passive"))
    )
    (net (code "67") (name "Net-(IC3-CH4)") (class "Default")
      (node (ref "IC3") (pin "5") (pinfunction "CH4_5") (pintype "bidirectional"))
      (node (ref "R13") (pin "1") (pinfunction "1_1") (pintype "passive"))
    )
    (net (code "68") (name "Net-(IC3-CH5)") (class "Default")
      (node (ref "IC3") (pin "6") (pinfunction "CH5_6") (pintype "bidirectional"))
      (node (ref "R14") (pin "1") (pinfunction "1_1") (pintype "passive"))
    )
    (net (code "69") (name "Net-(IC3-CH6)") (class "Default")
      (node (ref "IC3") (pin "7") (pinfunction "CH6_7") (pintype "bidirectional"))
      (node (ref "R15") (pin "1") (pinfunction "1_1") (pintype "passive"))
    )
    (net (code "70") (name "Net-(IC3-CH7)") (class "Default")
      (node (ref "IC3") (pin "8") (pinfunction "CH7_8") (pintype "bidirectional"))
      (node (ref "R16") (pin "1") (pinfunction "1_1") (pintype "passive"))
    )
    (net (code "71") (name "Net-(IC4-CH0)") (class "Default")
      (node (ref "IC4") (pin "1") (pinfunction "CH0_1") (pintype "bidirectional"))
      (node (ref "R17") (pin "1") (pinfunction "1_1") (pintype "passive"))
    )
    (net (code "72") (name "Net-(IC4-CH1)") (class "Default")
      (node (ref "IC4") (pin "2") (pinfunction "CH1_2") (pintype "bidirectional"))
      (node (ref "R18") (pin "1") (pinfunction "1_1") (pintype "passive"))
    )
    (net (code "73") (name "Net-(IC4-CH2)") (class "Default")
      (node (ref "IC4") (pin "3") (pinfunction "CH2_3") (pintype "bidirectional"))
      (node (ref "R19") (pin "1") (pinfunction "1_1") (pintype "passive"))
    )
    (net (code "74") (name "Net-(IC4-CH3)") (class "Default")
      (node (ref "IC4") (pin "4") (pinfunction "CH3_4") (pintype "bidirectional"))
      (node (ref "R20") (pin "1") (pinfunction "1_1") (pintype "passive"))
    )
    (net (code "75") (name "Net-(IC4-CH4)") (class "Default")
      (node (ref "IC4") (pin "5") (pinfunction "CH4_5") (pintype "bidirectional"))
      (node (ref "R21") (pin "1") (pinfunction "1_1") (pintype "passive"))
    )
    (net (code "76") (name "Net-(IC4-CH5)") (class "Default")
      (node (ref "IC4") (pin "6") (pinfunction "CH5_6") (pintype "bidirectional"))
      (node (ref "R22") (pin "1") (pinfunction "1_1") (pintype "passive"))
    )
    (net (code "77") (name "Net-(IC4-CH6)") (class "Default")
      (node (ref "IC4") (pin "7") (pinfunction "CH6_7") (pintype "bidirectional"))
      (node (ref "R23") (pin "1") (pinfunction "1_1") (pintype "passive"))
    )
    (net (code "78") (name "Net-(IC4-CH7)") (class "Default")
      (node (ref "IC4") (pin "8") (pinfunction "CH7_8") (pintype "bidirectional"))
      (node (ref "R24") (pin "1") (pinfunction "1_1") (pintype "passive"))
    )
    (net (code "79") (name "Net-(S1-2)") (class "Default")
      (node (ref "C1") (pin "1") (pinfunction "1_1") (pintype "passive"))
      (node (ref "R1") (pin "1") (pinfunction "1_1") (pintype "passive"))
      (node (ref "R2") (pin "1") (pinfunction "1_1") (pintype "passive"))
      (node (ref "S1") (pin "B2") (pinfunction "2_B2") (pintype "passive"))
    )
    (net (code "80") (name "unconnected-(GPIO_1-Pad1)") (class "Default")
      (node (ref "GPIO_1") (pin "1") (pinfunction "1_1") (pintype "passive"))
    )
    (net (code "81") (name "unconnected-(I2C_1-Pad1)") (class "Default")
      (node (ref "I2C_1") (pin "1") (pinfunction "1_1") (pintype "passive"))
    )
    (net (code "82") (name "unconnected-(I2C_2-Pad1)") (class "Default")
      (node (ref "I2C_2") (pin "1") (pinfunction "1_1") (pintype "passive"))
    )
    (net (code "83") (name "unconnected-(IC1-AN9{slash}RPA11{slash}RA11-Pad21)") (class "Default")
      (node (ref "IC1") (pin "21") (pinfunction "AN9/RPA11/RA11_21") (pintype "bidirectional"))
    )
    (net (code "84") (name "unconnected-(IC1-AN10{slash}RPA12{slash}RA12-Pad20)") (class "Default")
      (node (ref "IC1") (pin "20") (pinfunction "AN10/RPA12/RA12_20") (pintype "bidirectional"))
    )
    (net (code "85") (name "unconnected-(IC1-AN14{slash}CVD14{slash}RPE14{slash}FLT7{slash}PMPA1{slash}PSPA1_{slash}RE_14-Pad43)") (class "Default")
      (node (ref "IC1") (pin "43") (pinfunction "AN14/CVD14/RPE14/FLT7/PMPA1/PSPA1_/RE_14_43") (pintype "bidirectional"))
    )
    (net (code "86") (name "unconnected-(IC1-AN15{slash}CVD15{slash}RPE15{slash}FLT8{slash}PMPA0{slash}PSPA0{slash}RE15-Pad44)") (class "Default")
      (node (ref "IC1") (pin "44") (pinfunction "AN15/CVD15/RPE15/FLT8/PMPA0/PSPA0/RE15_44") (pintype "bidirectional"))
    )
    (net (code "87") (name "unconnected-(IC1-AN16{slash}RPG9{slash}PMA2{slash}RG9-Pad14)") (class "Default")
      (node (ref "IC1") (pin "14") (pinfunction "AN16/RPG9/PMA2/RG9_14") (pintype "bidirectional"))
    )
    (net (code "88") (name "unconnected-(IC1-AN20{slash}RE9-Pad19)") (class "Default")
      (node (ref "IC1") (pin "19") (pinfunction "AN20/RE9_19") (pintype "bidirectional"))
    )
    (net (code "89") (name "unconnected-(IC1-AN21{slash}RE8-Pad18)") (class "Default")
      (node (ref "IC1") (pin "18") (pinfunction "AN21/RE8_18") (pintype "bidirectional"))
    )
    (net (code "90") (name "unconnected-(IC1-AN22{slash}RG10-Pad17)") (class "Default")
      (node (ref "IC1") (pin "17") (pinfunction "AN22/RG10_17") (pintype "bidirectional"))
    )
    (net (code "91") (name "unconnected-(IC1-AN23{slash}PMA23{slash}RG15-Pad1)") (class "Default")
      (node (ref "IC1") (pin "1") (pinfunction "AN23/PMA23/RG15_1") (pintype "bidirectional"))
    )
    (net (code "92") (name "unconnected-(IC1-AN35{slash}CVD35{slash}RG11-Pad38)") (class "Default")
      (node (ref "IC1") (pin "38") (pinfunction "AN35/CVD35/RG11_38") (pintype "bidirectional"))
    )
    (net (code "93") (name "unconnected-(IC1-AN36{slash}CVD36{slash}RF13-Pad39)") (class "Default")
      (node (ref "IC1") (pin "39") (pinfunction "AN36/CVD36/RF13_39") (pintype "bidirectional"))
    )
    (net (code "94") (name "unconnected-(IC1-AN37{slash}CVD37{slash}RF12-Pad40)") (class "Default")
      (node (ref "IC1") (pin "40") (pinfunction "AN37/CVD37/RF12_40") (pintype "bidirectional"))
    )
    (net (code "95") (name "unconnected-(IC1-AN45{slash}CVD45{slash}RF5-Pad61)") (class "Default")
      (node (ref "IC1") (pin "61") (pinfunction "AN45/CVD45/RF5_61") (pintype "bidirectional"))
    )
    (net (code "96") (name "unconnected-(IC1-AN46{slash}CVD46{slash}RPA14{slash}RA14-Pad66)") (class "Default")
      (node (ref "IC1") (pin "66") (pinfunction "AN46/CVD46/RPA14/RA14_66") (pintype "bidirectional"))
    )
    (net (code "97") (name "unconnected-(IC1-AN47{slash}CVD47{slash}RPA15{slash}RA15-Pad67)") (class "Default")
      (node (ref "IC1") (pin "67") (pinfunction "AN47/CVD47/RPA15/RA15_67") (pintype "bidirectional"))
    )
    (net (code "98") (name "unconnected-(IC1-AN_11_{slash}CVD11_{slash}C11N2-{slash}FLT4{slash}PM_PA12{slash}RC11-Pad35)") (class "Default")
      (node (ref "IC1") (pin "35") (pinfunction "AN_11_/CVD11_/C11N2-/FLT4/PM_PA12/RC11_35") (pintype "bidirectional"))
    )
    (net (code "99") (name "unconnected-(IC1-D1--Pad56)") (class "Default")
      (node (ref "IC1") (pin "56") (pinfunction "D1-_56") (pintype "bidirectional"))
    )
    (net (code "100") (name "unconnected-(IC1-D1_+-Pad57)") (class "Default")
      (node (ref "IC1") (pin "57") (pinfunction "D1_+_57") (pintype "bidirectional"))
    )
    (net (code "101") (name "unconnected-(IC1-D2+-Pad60)") (class "Default")
      (node (ref "IC1") (pin "60") (pinfunction "D2+_60") (pintype "bidirectional"))
    )
    (net (code "102") (name "unconnected-(IC1-D2--Pad59)") (class "Default")
      (node (ref "IC1") (pin "59") (pinfunction "D2-_59") (pintype "bidirectional"))
    )
    (net (code "103") (name "unconnected-(IC1-OA20UT{slash}ANO{slash}C2IN4-{slash}C4IN3-{slash}RPAO{slash}RAO-Pad22)") (class "Default")
      (node (ref "IC1") (pin "22") (pinfunction "OA20UT/ANO/C2IN4-/C4IN3-/RPAO/RAO_22") (pintype "bidirectional"))
    )
    (net (code "104") (name "unconnected-(IC1-PMPD12{slash}RD12-Pad79)") (class "Default")
      (node (ref "IC1") (pin "79") (pinfunction "PMPD12/RD12_79") (pintype "bidirectional"))
    )
    (net (code "105") (name "unconnected-(IC1-PMPD13{slash}RD13-Pad80)") (class "Default")
      (node (ref "IC1") (pin "80") (pinfunction "PMPD13/RD13_80") (pintype "bidirectional"))
    )
    (net (code "106") (name "unconnected-(IC1-RD8-Pad68)") (class "Default")
      (node (ref "IC1") (pin "68") (pinfunction "RD8_68") (pintype "bidirectional"))
    )
    (net (code "107") (name "unconnected-(IC1-RPB12{slash}PWM2H{slash}PMPD2{slash}RB12-Pad98)") (class "Default")
      (node (ref "IC1") (pin "98") (pinfunction "RPB12/PWM2H/PMPD2/RB12_98") (pintype "bidirectional"))
    )
    (net (code "108") (name "unconnected-(IC1-RPB13{slash}PWM8H{slash}PWM2L{slash}CTPLS{slash}PMPD3{slash}RB13-Pad99)") (class "Default")
      (node (ref "IC1") (pin "99") (pinfunction "RPB13/PWM8H/PWM2L/CTPLS/PMPD3/RB13_99") (pintype "bidirectional"))
    )
    (net (code "109") (name "unconnected-(IC1-RPB14A{slash}BUSON1{slash}PMD6{slash}RB14-Pad4)") (class "Default")
      (node (ref "IC1") (pin "4") (pinfunction "RPB14A/BUSON1/PMD6/RB14_4") (pintype "bidirectional"))
    )
    (net (code "110") (name "unconnected-(IC1-RPC8{slash}PMPWR{slash}PSPWR{slash}RC8-Pad81)") (class "Default")
      (node (ref "IC1") (pin "81") (pinfunction "RPC8/PMPWR/PSPWR/RC8_81") (pintype "bidirectional"))
    )
    (net (code "111") (name "unconnected-(IC1-RPC9{slash}PMPD15{slash}RC9-Pad84)") (class "Default")
      (node (ref "IC1") (pin "84") (pinfunction "RPC9/PMPD15/RC9_84") (pintype "bidirectional"))
    )
    (net (code "112") (name "unconnected-(IC1-RPD6{slash}PWM12L{slash}PMPD14{slash}RD6-Pad83)") (class "Default")
      (node (ref "IC1") (pin "83") (pinfunction "RPD6/PWM12L/PMPD14/RD6_83") (pintype "bidirectional"))
    )
    (net (code "113") (name "unconnected-(IC1-SOSCI{slash}RPC13{slash}RC13-Pad73)") (class "Default")
      (node (ref "IC1") (pin "73") (pinfunction "SOSCI/RPC13/RC13_73") (pintype "bidirectional"))
    )
    (net (code "114") (name "unconnected-(IC1-TCK{slash}RPA7{slash}PMD5{slash}RA7-Pad3)") (class "Default")
      (node (ref "IC1") (pin "3") (pinfunction "TCK/RPA7/PMD5/RA7_3") (pintype "bidirectional"))
    )
    (net (code "115") (name "unconnected-(IC1-TDO{slash}PWM4H{slash}PMPD4{slash}RA10-Pad100)") (class "Default")
      (node (ref "IC1") (pin "100") (pinfunction "TDO/PWM4H/PMPD4/RA10_100") (pintype "bidirectional"))
    )
    (net (code "116") (name "unconnected-(IC1-TRCLK{slash}PMPA18{slash}RF6-Pad91)") (class "Default")
      (node (ref "IC1") (pin "91") (pinfunction "TRCLK/PMPA18/RF6_91") (pintype "bidirectional"))
    )
    (net (code "117") (name "unconnected-(IC1-TRD0{slash}PMPA22{slash}RG13-Pad97)") (class "Default")
      (node (ref "IC1") (pin "97") (pinfunction "TRD0/PMPA22/RG13_97") (pintype "bidirectional"))
    )
    (net (code "118") (name "unconnected-(IC1-TRD2{slash}PMPA20{slash}RG14-Pad95)") (class "Default")
      (node (ref "IC1") (pin "95") (pinfunction "TRD2/PMPA20/RG14_95") (pintype "bidirectional"))
    )
    (net (code "119") (name "unconnected-(IC1-TRD3{slash}PMPA19{slash}RF7-Pad92)") (class "Default")
      (node (ref "IC1") (pin "92") (pinfunction "TRD3/PMPA19/RF7_92") (pintype "bidirectional"))
    )
    (net (code "120") (name "unconnected-(IC1-VBUS-Pad54)") (class "Default")
      (node (ref "IC1") (pin "54") (pinfunction "VBUS_54") (pintype "bidirectional"))
    )
    (net (code "121") (name "unconnected-(IC1-VBUS2-Pad58)") (class "Default")
      (node (ref "IC1") (pin "58") (pinfunction "VBUS2_58") (pintype "bidirectional"))
    )
    (net (code "122") (name "unconnected-(IC1-VREF+{slash}AN34{slash}PMA6{slash}RF10-Pad29)") (class "Default")
      (node (ref "IC1") (pin "29") (pinfunction "VREF+/AN34/PMA6/RF10_29") (pintype "bidirectional"))
    )
    (net (code "123") (name "unconnected-(IC1-VREF-{slash}AN33{slash}PMA7{slash}RF9-Pad28)") (class "Default")
      (node (ref "IC1") (pin "28") (pinfunction "VREF-/AN33/PMA7/RF9_28") (pintype "bidirectional"))
    )
    (net (code "124") (name "unconnected-(IC2-A0-Pad1)") (class "Default")
      (node (ref "IC2") (pin "1") (pinfunction "A0_1") (pintype "bidirectional"))
    )
    (net (code "125") (name "unconnected-(IC2-A1-Pad2)") (class "Default")
      (node (ref "IC2") (pin "2") (pinfunction "A1_2") (pintype "bidirectional"))
    )
    (net (code "126") (name "unconnected-(IC3-BUSY-Pad16)") (class "Default")
      (node (ref "IC3") (pin "16") (pinfunction "BUSY_16") (pintype "bidirectional"))
    )
    (net (code "127") (name "unconnected-(IC4-BUSY-Pad16)") (class "Default")
      (node (ref "IC4") (pin "16") (pinfunction "BUSY_16") (pintype "bidirectional"))
    )
  )
)
